# MercurialSDR_FPGA_BNK.net
KiCad netlist of a schematic drawn in Altium Designer
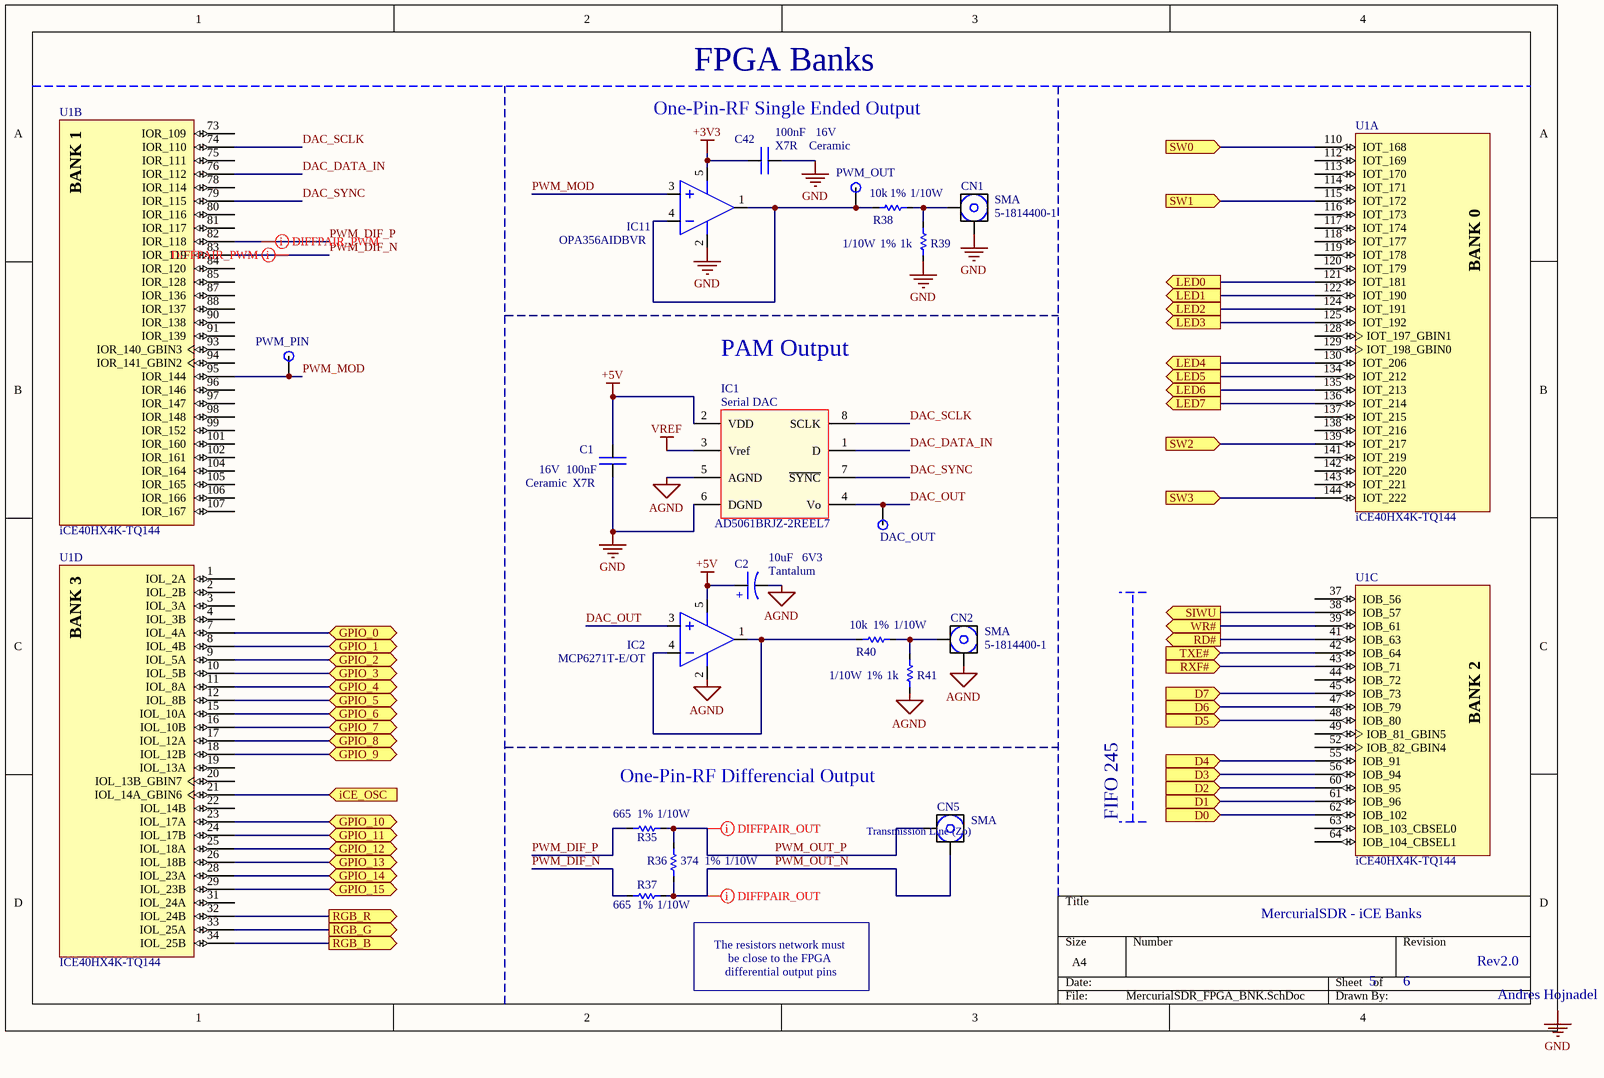
[diagram p0: MercurialSDR_FPGA_BNK.SchDoc]

(export (version "E")
  (design (tool "Eeschema 10.0.6"))
  (components
    (comp (ref "C1")
      (value "100nF")
      (footprint "CAP_0603")
      (description "Capacitor no polarizado")
      (fields
        (field (name "TEMP COEF") "X7R")
        (field (name "PART NUMBER") "CL10B104KO8NNNC")
        (field (name "VR") "16V")
        (field (name "MATERIAL") "Ceramic")
        (field (name "Comment") "Capacitor")
      )
      (libsource (lib "MercurialSDR") (part "Cap"))
    )
    (comp (ref "C2")
      (value "10uF")
      (footprint "CAP_TANT_1206")
      (description "Capacitor polarizado")
      (fields
        (field (name "PART NUMBER") "TAJA106K006RNJ")
        (field (name "VR") "6V3")
        (field (name "MATERIAL") "Tantalum")
        (field (name "Comment") "Capacitor Polarizado")
      )
      (libsource (lib "MercurialSDR") (part "Cap Pol"))
    )
    (comp (ref "C42")
      (value "100nF")
      (footprint "CAP_0603")
      (description "Capacitor no polarizado")
      (fields
        (field (name "TEMP COEF") "X7R")
        (field (name "PART NUMBER") "CL10B104KO8NNNC")
        (field (name "VR") "16V")
        (field (name "MATERIAL") "Ceramic")
        (field (name "Comment") "Capacitor")
      )
      (libsource (lib "MercurialSDR") (part "Cap"))
    )
    (comp (ref "CN1")
      (value "SMA")
      (footprint "SMA_Connector")
      (description "Conector SMA")
      (fields (field (name "PART NUMBER") "5-1814400-1"))
      (libsource (lib "MercurialSDR") (part "SMA"))
    )
    (comp (ref "CN2")
      (value "SMA")
      (footprint "SMA_Connector")
      (description "Conector SMA")
      (fields (field (name "PART NUMBER") "5-1814400-1"))
      (libsource (lib "MercurialSDR") (part "SMA"))
    )
    (comp (ref "CN5")
      (value "SMA")
      (footprint "SMA_Connector")
      (description "Conector SMA")
      (fields (field (name "PART NUMBER") "5-1814400-1"))
      (libsource (lib "MercurialSDR") (part "SMA"))
    )
    (comp (ref "IC1")
      (value "Serial DAC")
      (footprint "SOT-23-8")
      (description "DAC SPI")
      (fields (field (name "PART NUMBER") "AD5061BRJZ-2REEL7"))
      (libsource (lib "MercurialSDR") (part "AD5061"))
    )
    (comp (ref "IC2")
      (value "OPAMP")
      (footprint "SOT-23-5")
      (description "Operational Amplifier")
      (fields (field (name "PART NUMBER") "MCP6271T-E/OT"))
      (libsource (lib "MercurialSDR") (part "OPAMP"))
    )
    (comp (ref "IC11")
      (value "OPAMP")
      (footprint "SOT-23-5_2")
      (description "Operational Amplifier")
      (fields (field (name "PART NUMBER") "OPA356AIDBVR"))
      (libsource (lib "MercurialSDR") (part "OPAMP"))
    )
    (comp (ref "R35")
      (value "665")
      (footprint "RES_0603")
      (description "Resistor")
      (fields
        (field (name "POWER") "1/10W")
        (field (name "PART NUMBER") "RC0603FR-07665RL")
        (field (name "TOLERANCE") "1%")
        (field (name "Comment") "Resistor SMD")
      )
      (libsource (lib "MercurialSDR") (part "Res"))
    )
    (comp (ref "R36")
      (value "374")
      (footprint "RES_0603")
      (description "Resistor")
      (fields
        (field (name "POWER") "1/10W")
        (field (name "PART NUMBER") "RC0603FR-07374RL")
        (field (name "TOLERANCE") "1%")
        (field (name "Comment") "Resistor SMD")
      )
      (libsource (lib "MercurialSDR") (part "Res"))
    )
    (comp (ref "R37")
      (value "665")
      (footprint "RES_0603")
      (description "Resistor")
      (fields
        (field (name "POWER") "1/10W")
        (field (name "PART NUMBER") "RC0603FR-07665RL")
        (field (name "TOLERANCE") "1%")
        (field (name "Comment") "Resistor SMD")
      )
      (libsource (lib "MercurialSDR") (part "Res"))
    )
    (comp (ref "R38")
      (value "10k")
      (footprint "RES_0603")
      (description "Resistor")
      (fields
        (field (name "POWER") "1/10W")
        (field (name "PART NUMBER") "CR0603-FX-1002EAS")
        (field (name "TOLERANCE") "1%")
        (field (name "Comment") "Resistor SMD")
      )
      (libsource (lib "MercurialSDR") (part "Res"))
    )
    (comp (ref "R39")
      (value "1k")
      (footprint "RES_0603")
      (description "Resistor")
      (fields
        (field (name "POWER") "1/10W")
        (field (name "PART NUMBER") "CR0603-FX-1001ELF")
        (field (name "TOLERANCE") "1%")
        (field (name "Comment") "Resistor SMD")
      )
      (libsource (lib "MercurialSDR") (part "Res"))
    )
    (comp (ref "R40")
      (value "10k")
      (footprint "RES_0603")
      (description "Resistor")
      (fields
        (field (name "POWER") "1/10W")
        (field (name "PART NUMBER") "CR0603-FX-1002EAS")
        (field (name "TOLERANCE") "1%")
        (field (name "Comment") "Resistor SMD")
      )
      (libsource (lib "MercurialSDR") (part "Res"))
    )
    (comp (ref "R41")
      (value "1k")
      (footprint "RES_0603")
      (description "Resistor")
      (fields
        (field (name "POWER") "1/10W")
        (field (name "PART NUMBER") "CR0603-FX-1001ELF")
        (field (name "TOLERANCE") "1%")
        (field (name "Comment") "Resistor SMD")
      )
      (libsource (lib "MercurialSDR") (part "Res"))
    )
    (comp (ref "TP1")
      (value "Test Point")
      (footprint "TP_TOP")
      (fields (field (name "TP NAME") "PWM_PIN"))
      (libsource (lib "MercurialSDR") (part "Test Point"))
    )
    (comp (ref "TP2")
      (value "Test Point")
      (footprint "TP_TH")
      (fields (field (name "TP NAME") "DAC_OUT"))
      (libsource (lib "MercurialSDR") (part "Test Point"))
    )
    (comp (ref "TP5")
      (value "Test Point")
      (footprint "TP_TH")
      (fields (field (name "TP NAME") "PWM_OUT"))
      (libsource (lib "MercurialSDR") (part "Test Point"))
    )
    (comp (ref "U1")
      (value "iCE40HX4K-TQ144")
      (footprint "LATC-TQFP-144_L")
      (fields
        (field (name "MANUFACTURER") "Lattice Semiconductor")
        (field (name "PARTNUMBER") "ICE40HX4K-TQ144")
      )
      (libsource (lib "") (part "ICE40HX4K-TQ144_1"))
    )
  )
  (nets
    (net (code "1") (name "+3V3") (class "Default")
      (node (ref "C42") (pin "2") (pinfunction "2_2") (pintype "passive"))
      (node (ref "IC11") (pin "5") (pinfunction "VDD_5") (pintype "passive"))
    )
    (net (code "2") (name "+5V") (class "Default")
      (node (ref "C1") (pin "1") (pinfunction "1_1") (pintype "passive"))
      (node (ref "C2") (pin "1") (pinfunction "1_1") (pintype "passive"))
      (node (ref "IC1") (pin "2") (pinfunction "VDD_2") (pintype "passive"))
      (node (ref "IC2") (pin "5") (pinfunction "VDD_5") (pintype "passive"))
    )
    (net (code "3") (name "/D0") (class "Default")
      (node (ref "U1") (pin "62") (pinfunction "IOB_102_62") (pintype "bidirectional"))
    )
    (net (code "4") (name "/D1") (class "Default")
      (node (ref "U1") (pin "61") (pinfunction "IOB_96_61") (pintype "bidirectional"))
    )
    (net (code "5") (name "/D2") (class "Default")
      (node (ref "U1") (pin "60") (pinfunction "IOB_95_60") (pintype "bidirectional"))
    )
    (net (code "6") (name "/D3") (class "Default")
      (node (ref "U1") (pin "56") (pinfunction "IOB_94_56") (pintype "bidirectional"))
    )
    (net (code "7") (name "/D4") (class "Default")
      (node (ref "U1") (pin "55") (pinfunction "IOB_91_55") (pintype "bidirectional"))
    )
    (net (code "8") (name "/D5") (class "Default")
      (node (ref "U1") (pin "48") (pinfunction "IOB_80_48") (pintype "bidirectional"))
    )
    (net (code "9") (name "/D6") (class "Default")
      (node (ref "U1") (pin "47") (pinfunction "IOB_79_47") (pintype "bidirectional"))
    )
    (net (code "10") (name "/D7") (class "Default")
      (node (ref "U1") (pin "45") (pinfunction "IOB_73_45") (pintype "bidirectional"))
    )
    (net (code "11") (name "/DAC_DATA_IN") (class "Default")
      (node (ref "IC1") (pin "1") (pinfunction "D_1") (pintype "passive"))
      (node (ref "U1") (pin "76") (pinfunction "IOR_112_76") (pintype "bidirectional"))
    )
    (net (code "12") (name "/DAC_OUT") (class "Default")
      (node (ref "IC1") (pin "4") (pinfunction "Vo_4") (pintype "passive"))
      (node (ref "IC2") (pin "3") (pinfunction "V+_3") (pintype "passive"))
      (node (ref "TP2") (pin "1") (pinfunction "TP?_1") (pintype "passive"))
    )
    (net (code "13") (name "/DAC_SCLK") (class "Default")
      (node (ref "IC1") (pin "8") (pinfunction "SCLK_8") (pintype "passive"))
      (node (ref "U1") (pin "74") (pinfunction "IOR_110_74") (pintype "bidirectional"))
    )
    (net (code "14") (name "/DAC_SYNC") (class "Default")
      (node (ref "IC1") (pin "7") (pinfunction "~{SYNC}_7") (pintype "passive"))
      (node (ref "U1") (pin "79") (pinfunction "IOR_115_79") (pintype "bidirectional"))
    )
    (net (code "15") (name "/GPIO_0") (class "Default")
      (node (ref "U1") (pin "7") (pinfunction "IOL_4A_7") (pintype "bidirectional"))
    )
    (net (code "16") (name "/GPIO_1") (class "Default")
      (node (ref "U1") (pin "8") (pinfunction "IOL_4B_8") (pintype "bidirectional"))
    )
    (net (code "17") (name "/GPIO_2") (class "Default")
      (node (ref "U1") (pin "9") (pinfunction "IOL_5A_9") (pintype "bidirectional"))
    )
    (net (code "18") (name "/GPIO_3") (class "Default")
      (node (ref "U1") (pin "10") (pinfunction "IOL_5B_10") (pintype "bidirectional"))
    )
    (net (code "19") (name "/GPIO_4") (class "Default")
      (node (ref "U1") (pin "11") (pinfunction "IOL_8A_11") (pintype "bidirectional"))
    )
    (net (code "20") (name "/GPIO_5") (class "Default")
      (node (ref "U1") (pin "12") (pinfunction "IOL_8B_12") (pintype "bidirectional"))
    )
    (net (code "21") (name "/GPIO_6") (class "Default")
      (node (ref "U1") (pin "15") (pinfunction "IOL_10A_15") (pintype "bidirectional"))
    )
    (net (code "22") (name "/GPIO_7") (class "Default")
      (node (ref "U1") (pin "16") (pinfunction "IOL_10B_16") (pintype "bidirectional"))
    )
    (net (code "23") (name "/GPIO_8") (class "Default")
      (node (ref "U1") (pin "17") (pinfunction "IOL_12A_17") (pintype "bidirectional"))
    )
    (net (code "24") (name "/GPIO_9") (class "Default")
      (node (ref "U1") (pin "18") (pinfunction "IOL_12B_18") (pintype "bidirectional"))
    )
    (net (code "25") (name "/GPIO_10") (class "Default")
      (node (ref "U1") (pin "23") (pinfunction "IOL_17A_23") (pintype "bidirectional"))
    )
    (net (code "26") (name "/GPIO_11") (class "Default")
      (node (ref "U1") (pin "24") (pinfunction "IOL_17B_24") (pintype "bidirectional"))
    )
    (net (code "27") (name "/GPIO_12") (class "Default")
      (node (ref "U1") (pin "25") (pinfunction "IOL_18A_25") (pintype "bidirectional"))
    )
    (net (code "28") (name "/GPIO_13") (class "Default")
      (node (ref "U1") (pin "26") (pinfunction "IOL_18B_26") (pintype "bidirectional"))
    )
    (net (code "29") (name "/GPIO_14") (class "Default")
      (node (ref "U1") (pin "28") (pinfunction "IOL_23A_28") (pintype "bidirectional"))
    )
    (net (code "30") (name "/GPIO_15") (class "Default")
      (node (ref "U1") (pin "29") (pinfunction "IOL_23B_29") (pintype "bidirectional"))
    )
    (net (code "31") (name "/LED0") (class "Default")
      (node (ref "U1") (pin "121") (pinfunction "IOT_181_121") (pintype "bidirectional"))
    )
    (net (code "32") (name "/LED1") (class "Default")
      (node (ref "U1") (pin "122") (pinfunction "IOT_190_122") (pintype "bidirectional"))
    )
    (net (code "33") (name "/LED2") (class "Default")
      (node (ref "U1") (pin "124") (pinfunction "IOT_191_124") (pintype "bidirectional"))
    )
    (net (code "34") (name "/LED3") (class "Default")
      (node (ref "U1") (pin "125") (pinfunction "IOT_192_125") (pintype "bidirectional"))
    )
    (net (code "35") (name "/LED4") (class "Default")
      (node (ref "U1") (pin "130") (pinfunction "IOT_206_130") (pintype "bidirectional"))
    )
    (net (code "36") (name "/LED5") (class "Default")
      (node (ref "U1") (pin "134") (pinfunction "IOT_212_134") (pintype "bidirectional"))
    )
    (net (code "37") (name "/LED6") (class "Default")
      (node (ref "U1") (pin "135") (pinfunction "IOT_213_135") (pintype "bidirectional"))
    )
    (net (code "38") (name "/LED7") (class "Default")
      (node (ref "U1") (pin "136") (pinfunction "IOT_214_136") (pintype "bidirectional"))
    )
    (net (code "39") (name "/PWM_DIF_N") (class "Default")
      (node (ref "R37") (pin "2") (pinfunction "2_2") (pintype "passive"))
      (node (ref "U1") (pin "83") (pinfunction "IOR_119_83") (pintype "bidirectional"))
    )
    (net (code "40") (name "/PWM_DIF_P") (class "Default")
      (node (ref "R35") (pin "2") (pinfunction "2_2") (pintype "passive"))
      (node (ref "U1") (pin "82") (pinfunction "IOR_118_82") (pintype "bidirectional"))
    )
    (net (code "41") (name "/PWM_MOD") (class "Default")
      (node (ref "IC11") (pin "3") (pinfunction "V+_3") (pintype "passive"))
      (node (ref "TP1") (pin "1") (pinfunction "TP?_1") (pintype "passive"))
      (node (ref "U1") (pin "95") (pinfunction "IOR_144_95") (pintype "bidirectional"))
    )
    (net (code "42") (name "/PWM_OUT_N") (class "Default")
      (node (ref "CN5") (pin "2") (pinfunction "GND_2") (pintype "passive"))
      (node (ref "R36") (pin "2") (pinfunction "2_2") (pintype "passive"))
      (node (ref "R37") (pin "1") (pinfunction "1_1") (pintype "passive"))
    )
    (net (code "43") (name "/PWM_OUT_P") (class "Default")
      (node (ref "CN5") (pin "1") (pinfunction "Vin_1") (pintype "passive"))
      (node (ref "R35") (pin "1") (pinfunction "1_1") (pintype "passive"))
      (node (ref "R36") (pin "1") (pinfunction "1_1") (pintype "passive"))
    )
    (net (code "44") (name "/RD#") (class "Default")
      (node (ref "U1") (pin "41") (pinfunction "IOB_63_41") (pintype "bidirectional"))
    )
    (net (code "45") (name "/RGB_B") (class "Default")
      (node (ref "U1") (pin "34") (pinfunction "IOL_25B_34") (pintype "bidirectional"))
    )
    (net (code "46") (name "/RGB_G") (class "Default")
      (node (ref "U1") (pin "33") (pinfunction "IOL_25A_33") (pintype "bidirectional"))
    )
    (net (code "47") (name "/RGB_R") (class "Default")
      (node (ref "U1") (pin "32") (pinfunction "IOL_24B_32") (pintype "bidirectional"))
    )
    (net (code "48") (name "/RXF#") (class "Default")
      (node (ref "U1") (pin "43") (pinfunction "IOB_71_43") (pintype "bidirectional"))
    )
    (net (code "49") (name "/SIWU") (class "Default")
      (node (ref "U1") (pin "38") (pinfunction "IOB_57_38") (pintype "bidirectional"))
    )
    (net (code "50") (name "/SW0") (class "Default")
      (node (ref "U1") (pin "110") (pinfunction "IOT_168_110") (pintype "bidirectional"))
    )
    (net (code "51") (name "/SW1") (class "Default")
      (node (ref "U1") (pin "115") (pinfunction "IOT_172_115") (pintype "bidirectional"))
    )
    (net (code "52") (name "/SW2") (class "Default")
      (node (ref "U1") (pin "139") (pinfunction "IOT_217_139") (pintype "bidirectional"))
    )
    (net (code "53") (name "/SW3") (class "Default")
      (node (ref "U1") (pin "144") (pinfunction "IOT_222_144") (pintype "bidirectional"))
    )
    (net (code "54") (name "/TXE#") (class "Default")
      (node (ref "U1") (pin "42") (pinfunction "IOB_64_42") (pintype "bidirectional"))
    )
    (net (code "55") (name "/WR#") (class "Default")
      (node (ref "U1") (pin "39") (pinfunction "IOB_61_39") (pintype "bidirectional"))
    )
    (net (code "56") (name "/iCE_OSC") (class "Default")
      (node (ref "U1") (pin "21") (pinfunction "IOL_14A_GBIN6_21") (pintype "bidirectional"))
    )
    (net (code "57") (name "AGND") (class "Default")
      (node (ref "C2") (pin "2") (pinfunction "2_2") (pintype "passive"))
      (node (ref "CN2") (pin "2") (pinfunction "GND_2") (pintype "passive"))
      (node (ref "IC1") (pin "5") (pinfunction "AGND_5") (pintype "passive"))
      (node (ref "IC2") (pin "2") (pinfunction "Vss_2") (pintype "passive"))
      (node (ref "R41") (pin "2") (pinfunction "2_2") (pintype "passive"))
    )
    (net (code "58") (name "GND") (class "Default")
      (node (ref "C1") (pin "2") (pinfunction "2_2") (pintype "passive"))
      (node (ref "C42") (pin "1") (pinfunction "1_1") (pintype "passive"))
      (node (ref "CN1") (pin "2") (pinfunction "GND_2") (pintype "passive"))
      (node (ref "IC1") (pin "6") (pinfunction "DGND_6") (pintype "passive"))
      (node (ref "IC11") (pin "2") (pinfunction "Vss_2") (pintype "passive"))
      (node (ref "R39") (pin "2") (pinfunction "2_2") (pintype "passive"))
    )
    (net (code "59") (name "Net-(CN1-Vin)") (class "Default")
      (node (ref "CN1") (pin "1") (pinfunction "Vin_1") (pintype "passive"))
      (node (ref "R38") (pin "2") (pinfunction "2_2") (pintype "passive"))
      (node (ref "R39") (pin "1") (pinfunction "1_1") (pintype "passive"))
    )
    (net (code "60") (name "Net-(CN2-Vin)") (class "Default")
      (node (ref "CN2") (pin "1") (pinfunction "Vin_1") (pintype "passive"))
      (node (ref "R40") (pin "2") (pinfunction "2_2") (pintype "passive"))
      (node (ref "R41") (pin "1") (pinfunction "1_1") (pintype "passive"))
    )
    (net (code "61") (name "Net-(IC2-V-)") (class "Default")
      (node (ref "IC2") (pin "1") (pinfunction "Vo_1") (pintype "passive"))
      (node (ref "IC2") (pin "4") (pinfunction "V-_4") (pintype "passive"))
      (node (ref "R40") (pin "1") (pinfunction "1_1") (pintype "passive"))
    )
    (net (code "62") (name "Net-(IC11-V-)") (class "Default")
      (node (ref "IC11") (pin "1") (pinfunction "Vo_1") (pintype "passive"))
      (node (ref "IC11") (pin "4") (pinfunction "V-_4") (pintype "passive"))
      (node (ref "R38") (pin "1") (pinfunction "1_1") (pintype "passive"))
      (node (ref "TP5") (pin "1") (pinfunction "TP?_1") (pintype "passive"))
    )
    (net (code "63") (name "VREF") (class "Default")
      (node (ref "IC1") (pin "3") (pinfunction "Vref_3") (pintype "passive"))
    )
    (net (code "64") (name "unconnected-(U1A-IOT_169-Pad112)") (class "Default")
      (node (ref "U1") (pin "112") (pinfunction "IOT_169_112") (pintype "bidirectional"))
    )
    (net (code "65") (name "unconnected-(U1A-IOT_170-Pad113)") (class "Default")
      (node (ref "U1") (pin "113") (pinfunction "IOT_170_113") (pintype "bidirectional"))
    )
    (net (code "66") (name "unconnected-(U1A-IOT_171-Pad114)") (class "Default")
      (node (ref "U1") (pin "114") (pinfunction "IOT_171_114") (pintype "bidirectional"))
    )
    (net (code "67") (name "unconnected-(U1A-IOT_173-Pad116)") (class "Default")
      (node (ref "U1") (pin "116") (pinfunction "IOT_173_116") (pintype "bidirectional"))
    )
    (net (code "68") (name "unconnected-(U1A-IOT_174-Pad117)") (class "Default")
      (node (ref "U1") (pin "117") (pinfunction "IOT_174_117") (pintype "bidirectional"))
    )
    (net (code "69") (name "unconnected-(U1A-IOT_177-Pad118)") (class "Default")
      (node (ref "U1") (pin "118") (pinfunction "IOT_177_118") (pintype "bidirectional"))
    )
    (net (code "70") (name "unconnected-(U1A-IOT_178-Pad119)") (class "Default")
      (node (ref "U1") (pin "119") (pinfunction "IOT_178_119") (pintype "bidirectional"))
    )
    (net (code "71") (name "unconnected-(U1A-IOT_179-Pad120)") (class "Default")
      (node (ref "U1") (pin "120") (pinfunction "IOT_179_120") (pintype "bidirectional"))
    )
    (net (code "72") (name "unconnected-(U1A-IOT_197_GBIN1-Pad128)") (class "Default")
      (node (ref "U1") (pin "128") (pinfunction "IOT_197_GBIN1_128") (pintype "bidirectional"))
    )
    (net (code "73") (name "unconnected-(U1A-IOT_198_GBIN0-Pad129)") (class "Default")
      (node (ref "U1") (pin "129") (pinfunction "IOT_198_GBIN0_129") (pintype "bidirectional"))
    )
    (net (code "74") (name "unconnected-(U1A-IOT_215-Pad137)") (class "Default")
      (node (ref "U1") (pin "137") (pinfunction "IOT_215_137") (pintype "bidirectional"))
    )
    (net (code "75") (name "unconnected-(U1A-IOT_216-Pad138)") (class "Default")
      (node (ref "U1") (pin "138") (pinfunction "IOT_216_138") (pintype "bidirectional"))
    )
    (net (code "76") (name "unconnected-(U1A-IOT_219-Pad141)") (class "Default")
      (node (ref "U1") (pin "141") (pinfunction "IOT_219_141") (pintype "bidirectional"))
    )
    (net (code "77") (name "unconnected-(U1A-IOT_220-Pad142)") (class "Default")
      (node (ref "U1") (pin "142") (pinfunction "IOT_220_142") (pintype "bidirectional"))
    )
    (net (code "78") (name "unconnected-(U1A-IOT_221-Pad143)") (class "Default")
      (node (ref "U1") (pin "143") (pinfunction "IOT_221_143") (pintype "bidirectional"))
    )
    (net (code "79") (name "unconnected-(U1B-IOR_109-Pad73)") (class "Default")
      (node (ref "U1") (pin "73") (pinfunction "IOR_109_73") (pintype "bidirectional"))
    )
    (net (code "80") (name "unconnected-(U1B-IOR_111-Pad75)") (class "Default")
      (node (ref "U1") (pin "75") (pinfunction "IOR_111_75") (pintype "bidirectional"))
    )
    (net (code "81") (name "unconnected-(U1B-IOR_114-Pad78)") (class "Default")
      (node (ref "U1") (pin "78") (pinfunction "IOR_114_78") (pintype "bidirectional"))
    )
    (net (code "82") (name "unconnected-(U1B-IOR_116-Pad80)") (class "Default")
      (node (ref "U1") (pin "80") (pinfunction "IOR_116_80") (pintype "bidirectional"))
    )
    (net (code "83") (name "unconnected-(U1B-IOR_117-Pad81)") (class "Default")
      (node (ref "U1") (pin "81") (pinfunction "IOR_117_81") (pintype "bidirectional"))
    )
    (net (code "84") (name "unconnected-(U1B-IOR_120-Pad84)") (class "Default")
      (node (ref "U1") (pin "84") (pinfunction "IOR_120_84") (pintype "bidirectional"))
    )
    (net (code "85") (name "unconnected-(U1B-IOR_128-Pad85)") (class "Default")
      (node (ref "U1") (pin "85") (pinfunction "IOR_128_85") (pintype "bidirectional"))
    )
    (net (code "86") (name "unconnected-(U1B-IOR_136-Pad87)") (class "Default")
      (node (ref "U1") (pin "87") (pinfunction "IOR_136_87") (pintype "bidirectional"))
    )
    (net (code "87") (name "unconnected-(U1B-IOR_137-Pad88)") (class "Default")
      (node (ref "U1") (pin "88") (pinfunction "IOR_137_88") (pintype "bidirectional"))
    )
    (net (code "88") (name "unconnected-(U1B-IOR_138-Pad90)") (class "Default")
      (node (ref "U1") (pin "90") (pinfunction "IOR_138_90") (pintype "bidirectional"))
    )
    (net (code "89") (name "unconnected-(U1B-IOR_139-Pad91)") (class "Default")
      (node (ref "U1") (pin "91") (pinfunction "IOR_139_91") (pintype "bidirectional"))
    )
    (net (code "90") (name "unconnected-(U1B-IOR_140_GBIN3-Pad93)") (class "Default")
      (node (ref "U1") (pin "93") (pinfunction "IOR_140_GBIN3_93") (pintype "bidirectional"))
    )
    (net (code "91") (name "unconnected-(U1B-IOR_141_GBIN2-Pad94)") (class "Default")
      (node (ref "U1") (pin "94") (pinfunction "IOR_141_GBIN2_94") (pintype "bidirectional"))
    )
    (net (code "92") (name "unconnected-(U1B-IOR_146-Pad96)") (class "Default")
      (node (ref "U1") (pin "96") (pinfunction "IOR_146_96") (pintype "bidirectional"))
    )
    (net (code "93") (name "unconnected-(U1B-IOR_147-Pad97)") (class "Default")
      (node (ref "U1") (pin "97") (pinfunction "IOR_147_97") (pintype "bidirectional"))
    )
    (net (code "94") (name "unconnected-(U1B-IOR_148-Pad98)") (class "Default")
      (node (ref "U1") (pin "98") (pinfunction "IOR_148_98") (pintype "bidirectional"))
    )
    (net (code "95") (name "unconnected-(U1B-IOR_152-Pad99)") (class "Default")
      (node (ref "U1") (pin "99") (pinfunction "IOR_152_99") (pintype "bidirectional"))
    )
    (net (code "96") (name "unconnected-(U1B-IOR_160-Pad101)") (class "Default")
      (node (ref "U1") (pin "101") (pinfunction "IOR_160_101") (pintype "bidirectional"))
    )
    (net (code "97") (name "unconnected-(U1B-IOR_161-Pad102)") (class "Default")
      (node (ref "U1") (pin "102") (pinfunction "IOR_161_102") (pintype "bidirectional"))
    )
    (net (code "98") (name "unconnected-(U1B-IOR_164-Pad104)") (class "Default")
      (node (ref "U1") (pin "104") (pinfunction "IOR_164_104") (pintype "bidirectional"))
    )
    (net (code "99") (name "unconnected-(U1B-IOR_165-Pad105)") (class "Default")
      (node (ref "U1") (pin "105") (pinfunction "IOR_165_105") (pintype "bidirectional"))
    )
    (net (code "100") (name "unconnected-(U1B-IOR_166-Pad106)") (class "Default")
      (node (ref "U1") (pin "106") (pinfunction "IOR_166_106") (pintype "bidirectional"))
    )
    (net (code "101") (name "unconnected-(U1B-IOR_167-Pad107)") (class "Default")
      (node (ref "U1") (pin "107") (pinfunction "IOR_167_107") (pintype "bidirectional"))
    )
    (net (code "102") (name "unconnected-(U1C-IOB_56-Pad37)") (class "Default")
      (node (ref "U1") (pin "37") (pinfunction "IOB_56_37") (pintype "bidirectional"))
    )
    (net (code "103") (name "unconnected-(U1C-IOB_72-Pad44)") (class "Default")
      (node (ref "U1") (pin "44") (pinfunction "IOB_72_44") (pintype "bidirectional"))
    )
    (net (code "104") (name "unconnected-(U1C-IOB_81_GBIN5-Pad49)") (class "Default")
      (node (ref "U1") (pin "49") (pinfunction "IOB_81_GBIN5_49") (pintype "bidirectional"))
    )
    (net (code "105") (name "unconnected-(U1C-IOB_82_GBIN4-Pad52)") (class "Default")
      (node (ref "U1") (pin "52") (pinfunction "IOB_82_GBIN4_52") (pintype "bidirectional"))
    )
    (net (code "106") (name "unconnected-(U1C-IOB_103_CBSEL0-Pad63)") (class "Default")
      (node (ref "U1") (pin "63") (pinfunction "IOB_103_CBSEL0_63") (pintype "bidirectional"))
    )
    (net (code "107") (name "unconnected-(U1C-IOB_104_CBSEL1-Pad64)") (class "Default")
      (node (ref "U1") (pin "64") (pinfunction "IOB_104_CBSEL1_64") (pintype "bidirectional"))
    )
    (net (code "108") (name "unconnected-(U1D-IOL_2A-Pad1)") (class "Default")
      (node (ref "U1") (pin "1") (pinfunction "IOL_2A_1") (pintype "bidirectional"))
    )
    (net (code "109") (name "unconnected-(U1D-IOL_2B-Pad2)") (class "Default")
      (node (ref "U1") (pin "2") (pinfunction "IOL_2B_2") (pintype "bidirectional"))
    )
    (net (code "110") (name "unconnected-(U1D-IOL_3A-Pad3)") (class "Default")
      (node (ref "U1") (pin "3") (pinfunction "IOL_3A_3") (pintype "bidirectional"))
    )
    (net (code "111") (name "unconnected-(U1D-IOL_3B-Pad4)") (class "Default")
      (node (ref "U1") (pin "4") (pinfunction "IOL_3B_4") (pintype "bidirectional"))
    )
    (net (code "112") (name "unconnected-(U1D-IOL_13A-Pad19)") (class "Default")
      (node (ref "U1") (pin "19") (pinfunction "IOL_13A_19") (pintype "bidirectional"))
    )
    (net (code "113") (name "unconnected-(U1D-IOL_13B_GBIN7-Pad20)") (class "Default")
      (node (ref "U1") (pin "20") (pinfunction "IOL_13B_GBIN7_20") (pintype "bidirectional"))
    )
    (net (code "114") (name "unconnected-(U1D-IOL_14B-Pad22)") (class "Default")
      (node (ref "U1") (pin "22") (pinfunction "IOL_14B_22") (pintype "bidirectional"))
    )
    (net (code "115") (name "unconnected-(U1D-IOL_24A-Pad31)") (class "Default")
      (node (ref "U1") (pin "31") (pinfunction "IOL_24A_31") (pintype "bidirectional"))
    )
  )
)
